# SCH_Gardening_System_Monitor_2021-09-22.net
KiCad netlist of a schematic drawn in EasyEDA
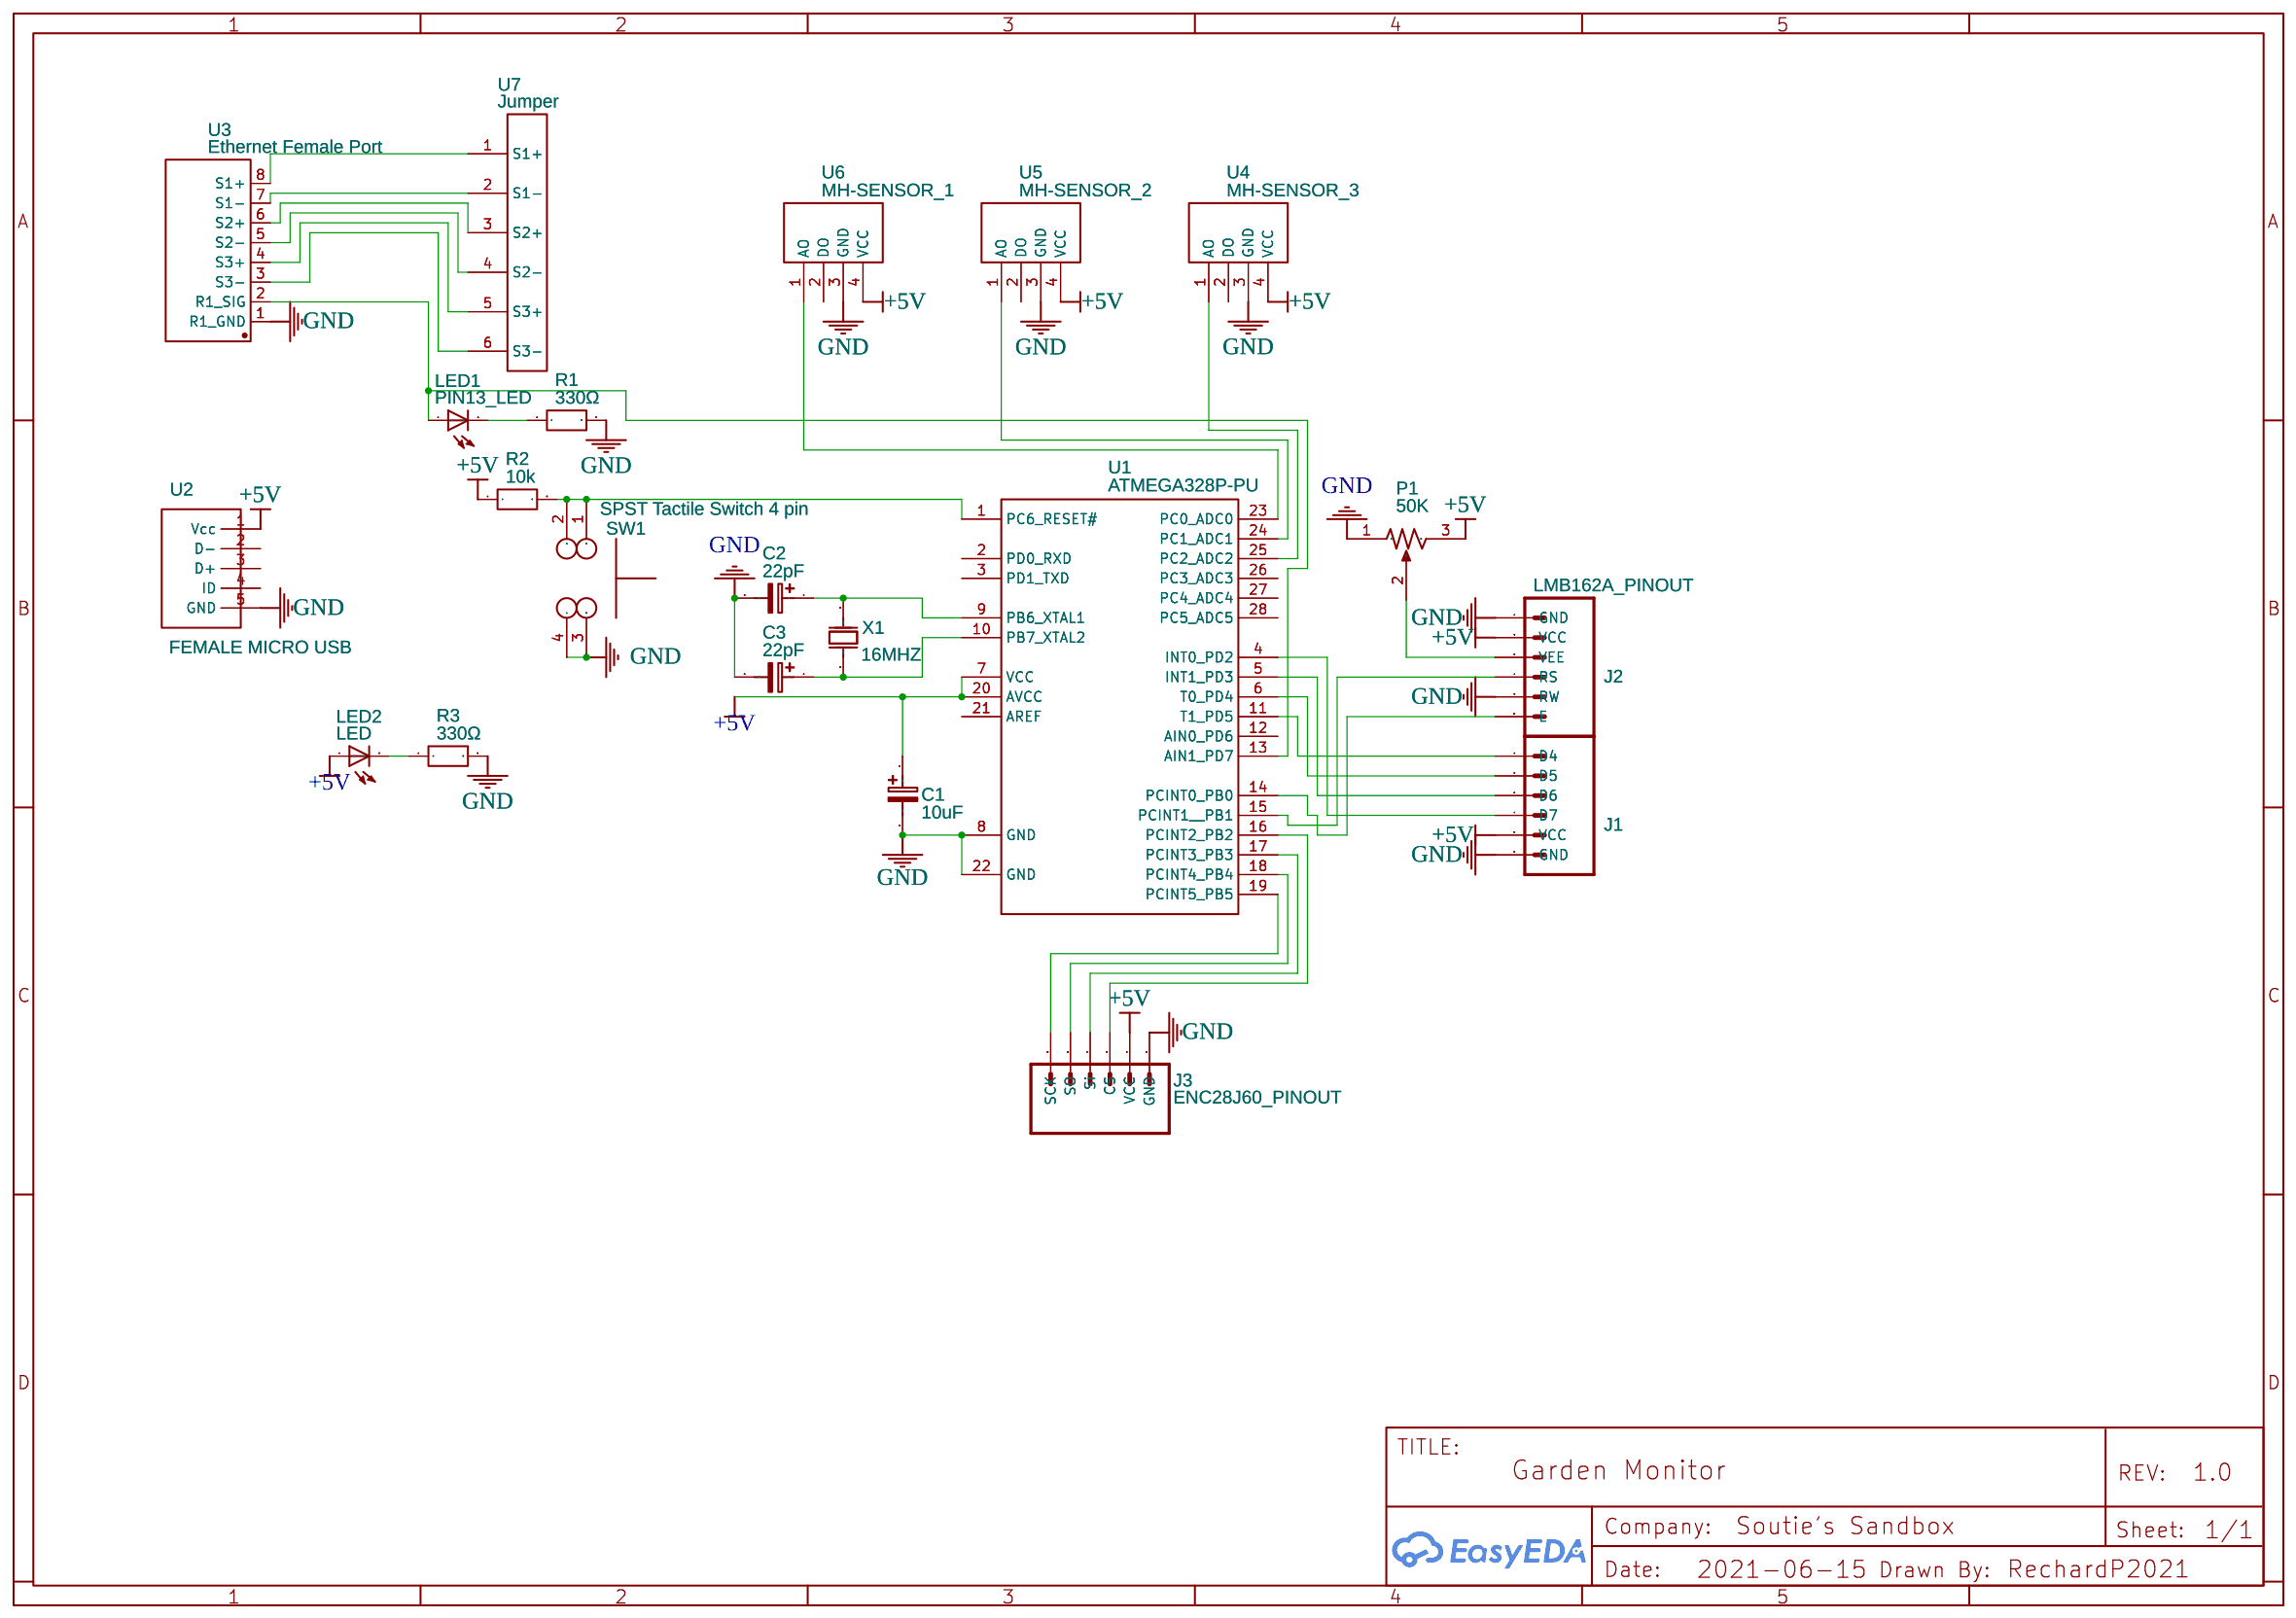
[diagram p0: schematic sheet]

(export (version "E")
  (design (tool "Eeschema 10.0.6"))
  (components
    (comp (ref "C1") (value "10uF") (libsource (lib "") (part "Capacitor")))
    (comp (ref "C2") (value "22pF") (libsource (lib "") (part "Capacitor_1")))
    (comp (ref "C3") (value "22pF") (libsource (lib "") (part "Capacitor_2")))
    (comp (ref "J1") (value "6_PIN_SERIAL_TARGET") (libsource (lib "") (part "6_PIN_SERIAL_TARGET_2")))
    (comp (ref "J2") (value "LMB162A_PINOUT") (libsource (lib "") (part "6_PIN_SERIAL_TARGET")))
    (comp (ref "J3") (value "ENC28J60_PINOUT") (libsource (lib "") (part "6_PIN_SERIAL_TARGET_1")))
    (comp (ref "LED1") (value "PIN13_LED") (libsource (lib "") (part "LED")))
    (comp (ref "LED2") (value "LED") (libsource (lib "") (part "LED")))
    (comp (ref "P1")
      (value "50K")
      (fields (field (name "BOM_Manufacturer Part") "pote 50k"))
      (libsource (lib "") (part "pote 50k"))
    )
    (comp (ref "R1")
      (value "330Ω")
      (fields
        (field (name "BOM_Manufacturer Part") "MF1/2W-100KΩ±1%T52")
        (field (name "BOM_Supplier Part") "C714085")
      )
      (libsource (lib "") (part "RESISTOR"))
    )
    (comp (ref "R2")
      (value "10k")
      (fields
        (field (name "BOM_Manufacturer Part") "MF1/2W-100KΩ±1%T52")
        (field (name "BOM_Supplier Part") "C714085")
      )
      (libsource (lib "") (part "RESISTOR"))
    )
    (comp (ref "R3")
      (value "330Ω")
      (fields
        (field (name "BOM_Manufacturer Part") "MF1/2W-100KΩ±1%T52")
        (field (name "BOM_Supplier Part") "C714085")
      )
      (libsource (lib "") (part "RESISTOR"))
    )
    (comp (ref "SW1")
      (value "SPST Tactile Switch 4 pin")
      (fields (field (name "BOM_Manufacturer Part") "C13828"))
      (libsource (lib "") (part "SPST Tactile Switch 4 pin"))
    )
    (comp (ref "U1")
      (value "ATMEGA328P-PU")
      (fields (field (name "BOM_Supplier Part") "C33901"))
      (libsource (lib "") (part "ATMEGA328P-PU"))
    )
    (comp (ref "U2")
      (value "FEMALE MICRO USB")
      (fields (field (name "BOM_Supplier Part") "C40953"))
      (libsource (lib "") (part "FEMALE MICRO USB"))
    )
    (comp (ref "U3") (value "Ethernet Female Port") (libsource (lib "") (part "Ethernet Female Port")))
    (comp (ref "U4")
      (value "MH-SENSOR_3")
      (fields (field (name "BOM_Manufacturer Part") "pin"))
      (libsource (lib "") (part "SCREEN PINS"))
    )
    (comp (ref "U5")
      (value "MH-SENSOR_2")
      (fields (field (name "BOM_Manufacturer Part") "pin"))
      (libsource (lib "") (part "SCREEN PINS"))
    )
    (comp (ref "U6")
      (value "MH-SENSOR_1")
      (fields (field (name "BOM_Manufacturer Part") "pin"))
      (libsource (lib "") (part "SCREEN PINS"))
    )
    (comp (ref "U7")
      (value "Jumper")
      (fields (field (name "BOM_Manufacturer Part") "pin3"))
      (libsource (lib "") (part "pin6"))
    )
    (comp (ref "X1")
      (value "16MHZ")
      (fields
        (field (name "BOM_Manufacturer Part") "X49SD16MSD2SC")
        (field (name "BOM_Supplier Part") "C16212")
      )
      (libsource (lib "") (part "16MHZ"))
    )
  )
  (nets
    (net (code "1") (name "+5V") (class "Default")
      (node (ref "C1") (pin "1") (pinfunction "1_1") (pintype "unspecified"))
      (node (ref "J1") (pin "5") (pinfunction "VCC_5") (pintype "bidirectional"))
      (node (ref "J2") (pin "2") (pinfunction "VCC_2") (pintype "bidirectional"))
      (node (ref "J3") (pin "2") (pinfunction "VCC_2") (pintype "bidirectional"))
      (node (ref "LED2") (pin "1") (pinfunction "A_1") (pintype "bidirectional"))
      (node (ref "P1") (pin "3") (pinfunction "3_3") (pintype "unspecified"))
      (node (ref "R2") (pin "1") (pinfunction "1_1") (pintype "unspecified"))
      (node (ref "U1") (pin "20") (pinfunction "AVCC_20") (pintype "passive"))
      (node (ref "U1") (pin "7") (pinfunction "VCC_7") (pintype "passive"))
      (node (ref "U2") (pin "1") (pinfunction "Vcc_1") (pintype "unspecified"))
      (node (ref "U4") (pin "4") (pinfunction "VCC_4") (pintype "unspecified"))
      (node (ref "U5") (pin "4") (pinfunction "VCC_4") (pintype "unspecified"))
      (node (ref "U6") (pin "4") (pinfunction "VCC_4") (pintype "unspecified"))
    )
    (net (code "2") (name "GND") (class "Default")
      (node (ref "C1") (pin "2") (pinfunction "2_2") (pintype "unspecified"))
      (node (ref "C2") (pin "2") (pinfunction "2_2") (pintype "unspecified"))
      (node (ref "C3") (pin "2") (pinfunction "2_2") (pintype "unspecified"))
      (node (ref "J1") (pin "6") (pinfunction "GND_6") (pintype "bidirectional"))
      (node (ref "J2") (pin "1") (pinfunction "GND_1") (pintype "bidirectional"))
      (node (ref "J2") (pin "5") (pinfunction "RW_5") (pintype "bidirectional"))
      (node (ref "J3") (pin "1") (pinfunction "GND_1") (pintype "bidirectional"))
      (node (ref "P1") (pin "1") (pinfunction "1_1") (pintype "unspecified"))
      (node (ref "R1") (pin "2") (pinfunction "2_2") (pintype "unspecified"))
      (node (ref "R3") (pin "2") (pinfunction "2_2") (pintype "unspecified"))
      (node (ref "SW1") (pin "3") (pinfunction "3_3") (pintype "unspecified"))
      (node (ref "SW1") (pin "4") (pinfunction "4_4") (pintype "unspecified"))
      (node (ref "U1") (pin "22") (pinfunction "GND_22") (pintype "passive"))
      (node (ref "U1") (pin "8") (pinfunction "GND_8") (pintype "passive"))
      (node (ref "U2") (pin "5") (pinfunction "GND_5") (pintype "unspecified"))
      (node (ref "U3") (pin "1") (pinfunction "R1_GND_1") (pintype "unspecified"))
      (node (ref "U4") (pin "3") (pinfunction "GND_3") (pintype "unspecified"))
      (node (ref "U5") (pin "3") (pinfunction "GND_3") (pintype "unspecified"))
      (node (ref "U6") (pin "3") (pinfunction "GND_3") (pintype "unspecified"))
    )
    (net (code "3") (name "Net-(J1-D4)") (class "Default")
      (node (ref "J1") (pin "1") (pinfunction "D4_1") (pintype "bidirectional"))
      (node (ref "U1") (pin "11") (pinfunction "T1_PD5_11") (pintype "bidirectional"))
    )
    (net (code "4") (name "Net-(J1-D5)") (class "Default")
      (node (ref "J1") (pin "2") (pinfunction "D5_2") (pintype "bidirectional"))
      (node (ref "U1") (pin "6") (pinfunction "T0_PD4_6") (pintype "bidirectional"))
    )
    (net (code "5") (name "Net-(J1-D6)") (class "Default")
      (node (ref "J1") (pin "3") (pinfunction "D6_3") (pintype "bidirectional"))
      (node (ref "U1") (pin "5") (pinfunction "INT1_PD3_5") (pintype "bidirectional"))
    )
    (net (code "6") (name "Net-(J1-D7)") (class "Default")
      (node (ref "J1") (pin "4") (pinfunction "D7_4") (pintype "bidirectional"))
      (node (ref "U1") (pin "4") (pinfunction "INT0_PD2_4") (pintype "bidirectional"))
    )
    (net (code "7") (name "Net-(J2-E)") (class "Default")
      (node (ref "J2") (pin "6") (pinfunction "E_6") (pintype "bidirectional"))
      (node (ref "U1") (pin "14") (pinfunction "PCINT0_PB0_14") (pintype "bidirectional"))
    )
    (net (code "8") (name "Net-(J2-RS)") (class "Default")
      (node (ref "J2") (pin "4") (pinfunction "RS_4") (pintype "bidirectional"))
      (node (ref "U1") (pin "15") (pinfunction "PCINT1__PB1_15") (pintype "bidirectional"))
    )
    (net (code "9") (name "Net-(J2-VEE)") (class "Default")
      (node (ref "J2") (pin "3") (pinfunction "VEE_3") (pintype "bidirectional"))
      (node (ref "P1") (pin "2") (pinfunction "2_2") (pintype "unspecified"))
    )
    (net (code "10") (name "Net-(J3-CS)") (class "Default")
      (node (ref "J3") (pin "3") (pinfunction "CS_3") (pintype "bidirectional"))
      (node (ref "U1") (pin "16") (pinfunction "PCINT2_PB2_16") (pintype "bidirectional"))
    )
    (net (code "11") (name "Net-(J3-SCK)") (class "Default")
      (node (ref "J3") (pin "6") (pinfunction "SCK_6") (pintype "bidirectional"))
      (node (ref "U1") (pin "19") (pinfunction "PCINT5_PB5_19") (pintype "bidirectional"))
    )
    (net (code "12") (name "Net-(J3-SO)") (class "Default")
      (node (ref "J3") (pin "5") (pinfunction "SO_5") (pintype "bidirectional"))
      (node (ref "U1") (pin "18") (pinfunction "PCINT4_PB4_18") (pintype "bidirectional"))
    )
    (net (code "13") (name "Net-(J3-Si)") (class "Default")
      (node (ref "J3") (pin "4") (pinfunction "Si_4") (pintype "bidirectional"))
      (node (ref "U1") (pin "17") (pinfunction "PCINT3_PB3_17") (pintype "bidirectional"))
    )
    (net (code "14") (name "Net-(LED1-A)") (class "Default")
      (node (ref "LED1") (pin "1") (pinfunction "A_1") (pintype "bidirectional"))
      (node (ref "U1") (pin "13") (pinfunction "AIN1_PD7_13") (pintype "bidirectional"))
      (node (ref "U3") (pin "2") (pinfunction "R1_SIG_2") (pintype "unspecified"))
    )
    (net (code "15") (name "Net-(LED1-C)") (class "Default")
      (node (ref "LED1") (pin "2") (pinfunction "C_2") (pintype "bidirectional"))
      (node (ref "R1") (pin "1") (pinfunction "1_1") (pintype "unspecified"))
    )
    (net (code "16") (name "Net-(LED2-C)") (class "Default")
      (node (ref "LED2") (pin "2") (pinfunction "C_2") (pintype "bidirectional"))
      (node (ref "R3") (pin "1") (pinfunction "1_1") (pintype "unspecified"))
    )
    (net (code "17") (name "Net-(U1-PB6_XTAL1)") (class "Default")
      (node (ref "C2") (pin "1") (pinfunction "1_1") (pintype "unspecified"))
      (node (ref "U1") (pin "9") (pinfunction "PB6_XTAL1_9") (pintype "bidirectional"))
      (node (ref "X1") (pin "2") (pinfunction "OSC2_2") (pintype "input"))
    )
    (net (code "18") (name "Net-(U1-PB7_XTAL2)") (class "Default")
      (node (ref "C3") (pin "1") (pinfunction "1_1") (pintype "unspecified"))
      (node (ref "U1") (pin "10") (pinfunction "PB7_XTAL2_10") (pintype "bidirectional"))
      (node (ref "X1") (pin "1") (pinfunction "OSC1_1") (pintype "input"))
    )
    (net (code "19") (name "Net-(U1-PC0_ADC0)") (class "Default")
      (node (ref "U1") (pin "23") (pinfunction "PC0_ADC0_23") (pintype "bidirectional"))
      (node (ref "U6") (pin "1") (pinfunction "AO_1") (pintype "unspecified"))
    )
    (net (code "20") (name "Net-(U1-PC1_ADC1)") (class "Default")
      (node (ref "U1") (pin "24") (pinfunction "PC1_ADC1_24") (pintype "bidirectional"))
      (node (ref "U5") (pin "1") (pinfunction "AO_1") (pintype "unspecified"))
    )
    (net (code "21") (name "Net-(U1-PC2_ADC2)") (class "Default")
      (node (ref "U1") (pin "25") (pinfunction "PC2_ADC2_25") (pintype "bidirectional"))
      (node (ref "U4") (pin "1") (pinfunction "AO_1") (pintype "unspecified"))
    )
    (net (code "22") (name "Net-(U1-PC6_RESET#)") (class "Default")
      (node (ref "R2") (pin "2") (pinfunction "2_2") (pintype "unspecified"))
      (node (ref "SW1") (pin "1") (pinfunction "1_1") (pintype "unspecified"))
      (node (ref "SW1") (pin "2") (pinfunction "2_2") (pintype "unspecified"))
      (node (ref "U1") (pin "1") (pinfunction "PC6_RESET#_1") (pintype "bidirectional"))
    )
    (net (code "23") (name "Net-(U3-S1+)") (class "Default")
      (node (ref "U3") (pin "8") (pinfunction "S1+_8") (pintype "unspecified"))
      (node (ref "U7") (pin "1") (pinfunction "S1+_1") (pintype "unspecified"))
    )
    (net (code "24") (name "Net-(U3-S1-)") (class "Default")
      (node (ref "U3") (pin "7") (pinfunction "S1-_7") (pintype "unspecified"))
      (node (ref "U7") (pin "2") (pinfunction "S1-_2") (pintype "unspecified"))
    )
    (net (code "25") (name "Net-(U3-S2+)") (class "Default")
      (node (ref "U3") (pin "6") (pinfunction "S2+_6") (pintype "unspecified"))
      (node (ref "U7") (pin "3") (pinfunction "S2+_3") (pintype "unspecified"))
    )
    (net (code "26") (name "Net-(U3-S2-)") (class "Default")
      (node (ref "U3") (pin "5") (pinfunction "S2-_5") (pintype "unspecified"))
      (node (ref "U7") (pin "4") (pinfunction "S2-_4") (pintype "unspecified"))
    )
    (net (code "27") (name "Net-(U3-S3+)") (class "Default")
      (node (ref "U3") (pin "4") (pinfunction "S3+_4") (pintype "unspecified"))
      (node (ref "U7") (pin "5") (pinfunction "S3+_5") (pintype "unspecified"))
    )
    (net (code "28") (name "Net-(U3-S3-)") (class "Default")
      (node (ref "U3") (pin "3") (pinfunction "S3-_3") (pintype "unspecified"))
      (node (ref "U7") (pin "6") (pinfunction "S3-_6") (pintype "unspecified"))
    )
    (net (code "29") (name "unconnected-(U1-AIN0_PD6-Pad12)") (class "Default")
      (node (ref "U1") (pin "12") (pinfunction "AIN0_PD6_12") (pintype "bidirectional"))
    )
    (net (code "30") (name "unconnected-(U1-AREF-Pad21)") (class "Default")
      (node (ref "U1") (pin "21") (pinfunction "AREF_21") (pintype "passive"))
    )
    (net (code "31") (name "unconnected-(U1-PC3_ADC3-Pad26)") (class "Default")
      (node (ref "U1") (pin "26") (pinfunction "PC3_ADC3_26") (pintype "bidirectional"))
    )
    (net (code "32") (name "unconnected-(U1-PC4_ADC4-Pad27)") (class "Default")
      (node (ref "U1") (pin "27") (pinfunction "PC4_ADC4_27") (pintype "bidirectional"))
    )
    (net (code "33") (name "unconnected-(U1-PC5_ADC5-Pad28)") (class "Default")
      (node (ref "U1") (pin "28") (pinfunction "PC5_ADC5_28") (pintype "bidirectional"))
    )
    (net (code "34") (name "unconnected-(U1-PD0_RXD-Pad2)") (class "Default")
      (node (ref "U1") (pin "2") (pinfunction "PD0_RXD_2") (pintype "bidirectional"))
    )
    (net (code "35") (name "unconnected-(U1-PD1_TXD-Pad3)") (class "Default")
      (node (ref "U1") (pin "3") (pinfunction "PD1_TXD_3") (pintype "bidirectional"))
    )
    (net (code "36") (name "unconnected-(U2-D+-Pad3)") (class "Default")
      (node (ref "U2") (pin "3") (pinfunction "D+_3") (pintype "unspecified"))
    )
    (net (code "37") (name "unconnected-(U2-D--Pad2)") (class "Default")
      (node (ref "U2") (pin "2") (pinfunction "D-_2") (pintype "unspecified"))
    )
    (net (code "38") (name "unconnected-(U2-ID-Pad4)") (class "Default")
      (node (ref "U2") (pin "4") (pinfunction "ID_4") (pintype "unspecified"))
    )
    (net (code "39") (name "unconnected-(U4-DO-Pad2)") (class "Default")
      (node (ref "U4") (pin "2") (pinfunction "DO_2") (pintype "unspecified"))
    )
    (net (code "40") (name "unconnected-(U5-DO-Pad2)") (class "Default")
      (node (ref "U5") (pin "2") (pinfunction "DO_2") (pintype "unspecified"))
    )
    (net (code "41") (name "unconnected-(U6-DO-Pad2)") (class "Default")
      (node (ref "U6") (pin "2") (pinfunction "DO_2") (pintype "unspecified"))
    )
  )
)
